# SDCard.net
KiCad netlist of a schematic drawn in Altium Designer
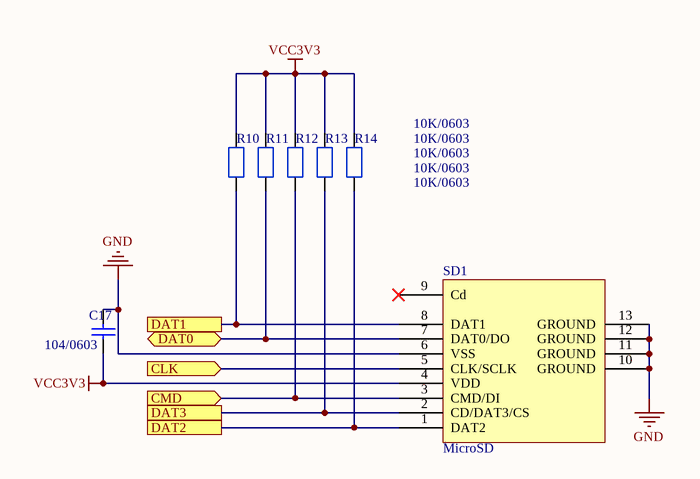
[diagram p0: SDCard.SchDoc]

(export (version "E")
  (design (tool "Eeschema 10.0.6"))
  (components
    (comp (ref "C17")
      (value "104/0603")
      (footprint "C0603")
      (description "无极性贴片电容")
      (libsource (lib "常用原件") (part "CAP"))
    )
    (comp (ref "R10") (value "10K/0603") (footprint "R0603") (libsource (lib "常用原件") (part "RES")))
    (comp (ref "R11") (value "10K/0603") (footprint "R0603") (libsource (lib "常用原件") (part "RES")))
    (comp (ref "R12") (value "10K/0603") (footprint "R0603") (libsource (lib "常用原件") (part "RES")))
    (comp (ref "R13") (value "10K/0603") (footprint "R0603") (libsource (lib "常用原件") (part "RES")))
    (comp (ref "R14") (value "10K/0603") (footprint "R0603") (libsource (lib "常用原件") (part "RES")))
    (comp (ref "SD1")
      (value "MicroSD")
      (footprint "SD_Card_M")
      (description "TF卡槽")
      (libsource (lib "常用原件") (part "MicroSD"))
    )
  )
  (nets
    (net (code "1") (name "/CLK") (class "Default")
      (node (ref "SD1") (pin "5") (pinfunction "CLK/SCLK_5") (pintype "passive"))
    )
    (net (code "2") (name "/CMD") (class "Default")
      (node (ref "R12") (pin "1") (pinfunction "1_1") (pintype "passive"))
      (node (ref "SD1") (pin "3") (pinfunction "CMD/DI_3") (pintype "passive"))
    )
    (net (code "3") (name "/DAT0") (class "Default")
      (node (ref "R11") (pin "1") (pinfunction "1_1") (pintype "passive"))
      (node (ref "SD1") (pin "7") (pinfunction "DAT0/DO_7") (pintype "passive"))
    )
    (net (code "4") (name "/DAT1") (class "Default")
      (node (ref "R10") (pin "1") (pinfunction "1_1") (pintype "passive"))
      (node (ref "SD1") (pin "8") (pinfunction "DAT1_8") (pintype "passive"))
    )
    (net (code "5") (name "/DAT2") (class "Default")
      (node (ref "R14") (pin "1") (pinfunction "1_1") (pintype "passive"))
      (node (ref "SD1") (pin "1") (pinfunction "DAT2_1") (pintype "passive"))
    )
    (net (code "6") (name "/DAT3") (class "Default")
      (node (ref "R13") (pin "1") (pinfunction "1_1") (pintype "passive"))
      (node (ref "SD1") (pin "2") (pinfunction "CD/DAT3/CS_2") (pintype "passive"))
    )
    (net (code "7") (name "GND") (class "Default")
      (node (ref "C17") (pin "2") (pinfunction "2_2") (pintype "passive"))
      (node (ref "SD1") (pin "10") (pinfunction "GROUND_10") (pintype "passive"))
      (node (ref "SD1") (pin "11") (pinfunction "GROUND_11") (pintype "passive"))
      (node (ref "SD1") (pin "12") (pinfunction "GROUND_12") (pintype "passive"))
      (node (ref "SD1") (pin "13") (pinfunction "GROUND_13") (pintype "passive"))
      (node (ref "SD1") (pin "6") (pinfunction "VSS_6") (pintype "passive"))
    )
    (net (code "8") (name "VCC3V3") (class "Default")
      (node (ref "C17") (pin "1") (pinfunction "1_1") (pintype "passive"))
      (node (ref "R10") (pin "2") (pinfunction "2_2") (pintype "passive"))
      (node (ref "R11") (pin "2") (pinfunction "2_2") (pintype "passive"))
      (node (ref "R12") (pin "2") (pinfunction "2_2") (pintype "passive"))
      (node (ref "R13") (pin "2") (pinfunction "2_2") (pintype "passive"))
      (node (ref "R14") (pin "2") (pinfunction "2_2") (pintype "passive"))
      (node (ref "SD1") (pin "4") (pinfunction "VDD_4") (pintype "passive"))
    )
    (net (code "9") (name "unconnected-(SD1-Cd-Pad9)") (class "Default")
      (node (ref "SD1") (pin "9") (pinfunction "Cd_9") (pintype "passive+no_connect"))
    )
  )
)
